# Dogfish3D_-_Z_Driver.net
KiCad netlist of a schematic drawn in Altium Designer
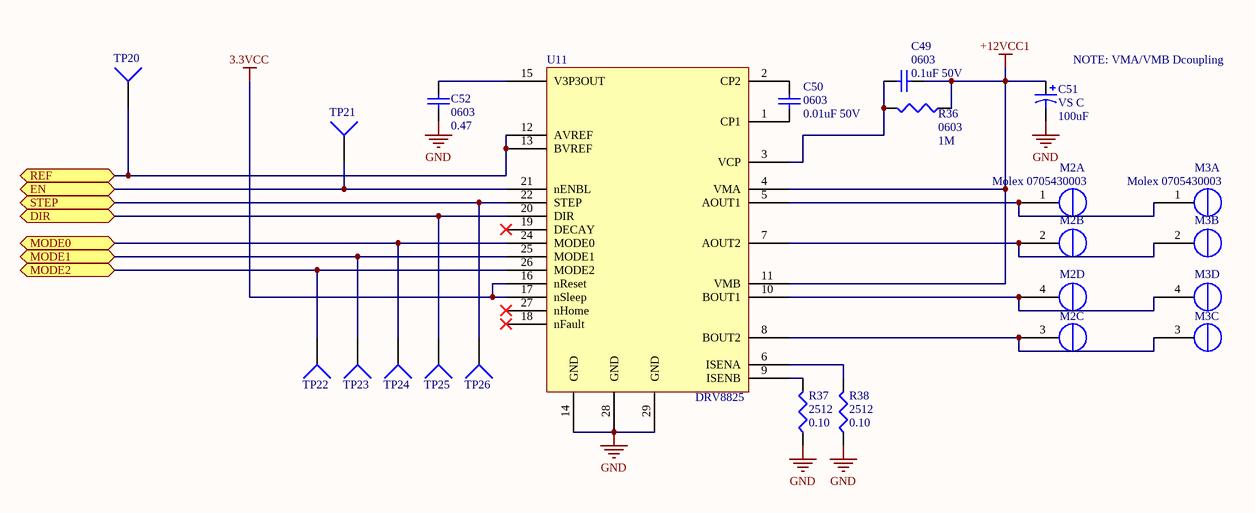
[diagram p0: Dogfish3D - Z Driver.SchDoc]

(export (version "E")
  (design (tool "Eeschema 10.0.6"))
  (components
    (comp (ref "C49")
      (value "0603")
      (footprint "1608[0603]")
      (description "Capacitor (Semiconductor SIM Model)")
      (fields (field (name "ALTIUM_VALUE") "0.1uF 50V") (field (name "PUBLISHER") "Altium Limited"))
      (libsource (lib "Miscellaneous Devices") (part "Cap Semi"))
    )
    (comp (ref "C50")
      (value "0603")
      (footprint "1608[0603]")
      (description "Capacitor (Semiconductor SIM Model)")
      (fields (field (name "ALTIUM_VALUE") "0.01uF 50V") (field (name "PUBLISHER") "Altium Limited"))
      (libsource (lib "Miscellaneous Devices") (part "Cap Semi"))
    )
    (comp (ref "C51")
      (value "VS C")
      (footprint "Panasonic VS C")
      (description "Polarized Capacitor (Radial)")
      (fields (field (name "ALTIUM_VALUE") "100uF") (field (name "PUBLISHER") "Altium Limited"))
      (libsource (lib "Miscellaneous Devices") (part "Cap Pol1"))
    )
    (comp (ref "C52")
      (value "0603")
      (footprint "1608[0603]")
      (description "Capacitor (Semiconductor SIM Model)")
      (fields (field (name "ALTIUM_VALUE") "0.47") (field (name "PUBLISHER") "Altium Limited"))
      (libsource (lib "Miscellaneous Devices") (part "Cap Semi"))
    )
    (comp (ref "M2")
      (value "Molex 0705430003")
      (footprint "Molex 0705430003")
      (description "Molex 4 Pin Clip Connector")
      (libsource (lib "ZMBo Schematic Library") (part "Molex 0705430003 Alt"))
    )
    (comp (ref "M3")
      (value "Molex 0705430003")
      (footprint "4POL254")
      (description "Molex 4 Pin Clip Connector")
      (libsource (lib "ZMBo Schematic Library") (part "Molex 0705430003 Alt"))
    )
    (comp (ref "R36")
      (value "0603")
      (footprint "J1-0603")
      (description "Resistor")
      (fields (field (name "ALTIUM_VALUE") "1M") (field (name "PUBLISHER") "Altium Limited"))
      (libsource (lib "Miscellaneous Devices") (part "Res3"))
    )
    (comp (ref "R37")
      (value "2512")
      (footprint "Resistor2512")
      (description "Resistor")
      (fields (field (name "ALTIUM_VALUE") "0.10") (field (name "PUBLISHER") "Altium Limited"))
      (libsource (lib "Miscellaneous Devices") (part "Res3"))
    )
    (comp (ref "R38")
      (value "2512")
      (footprint "Resistor2512")
      (description "Resistor")
      (fields (field (name "ALTIUM_VALUE") "0.10") (field (name "PUBLISHER") "Altium Limited"))
      (libsource (lib "Miscellaneous Devices") (part "Res3"))
    )
    (comp (ref "TP20")
      (value "TP4")
      (footprint "TP-2")
      (description "Socket")
      (fields (field (name "PUBLISHER") "Altium Limited"))
      (libsource (lib "ZMBo Schematic Library") (part "Socket"))
    )
    (comp (ref "TP21")
      (value "TP4")
      (footprint "TP-2")
      (description "Socket")
      (fields (field (name "PUBLISHER") "Altium Limited"))
      (libsource (lib "ZMBo Schematic Library") (part "Socket"))
    )
    (comp (ref "TP22")
      (value "TP4")
      (footprint "TP-2")
      (description "Socket")
      (fields (field (name "PUBLISHER") "Altium Limited"))
      (libsource (lib "ZMBo Schematic Library") (part "Socket"))
    )
    (comp (ref "TP23")
      (value "TP4")
      (footprint "TP-2")
      (description "Socket")
      (fields (field (name "PUBLISHER") "Altium Limited"))
      (libsource (lib "ZMBo Schematic Library") (part "Socket"))
    )
    (comp (ref "TP24")
      (value "TP4")
      (footprint "TP-2")
      (description "Socket")
      (fields (field (name "PUBLISHER") "Altium Limited"))
      (libsource (lib "ZMBo Schematic Library") (part "Socket"))
    )
    (comp (ref "TP25")
      (value "TP4")
      (footprint "TP-2")
      (description "Socket")
      (fields (field (name "PUBLISHER") "Altium Limited"))
      (libsource (lib "ZMBo Schematic Library") (part "Socket"))
    )
    (comp (ref "TP26")
      (value "TP4")
      (footprint "TP-2")
      (description "Socket")
      (fields (field (name "PUBLISHER") "Altium Limited"))
      (libsource (lib "ZMBo Schematic Library") (part "Socket"))
    )
    (comp (ref "U11")
      (value "DRV8825")
      (footprint "DRV8825")
      (description "DRV8825 Ti Stepper Driver")
      (libsource (lib "ZMBo Schematic Library") (part "DRV8825"))
    )
  )
  (nets
    (net (code "1") (name "+12VCC1") (class "Default")
      (node (ref "C49") (pin "1") (pinfunction "1_1") (pintype "passive"))
      (node (ref "C51") (pin "1") (pinfunction "1_1") (pintype "passive"))
      (node (ref "R36") (pin "1") (pinfunction "1_1") (pintype "passive"))
      (node (ref "U11") (pin "11") (pinfunction "VMB_11") (pintype "passive"))
      (node (ref "U11") (pin "4") (pinfunction "VMA_4") (pintype "passive"))
    )
    (net (code "2") (name "/DIR") (class "Default")
      (node (ref "TP25") (pin "1") (pinfunction "1_1") (pintype "passive"))
      (node (ref "U11") (pin "20") (pinfunction "DIR_20") (pintype "passive"))
    )
    (net (code "3") (name "/EN") (class "Default")
      (node (ref "TP21") (pin "1") (pinfunction "1_1") (pintype "passive"))
      (node (ref "U11") (pin "21") (pinfunction "nENBL_21") (pintype "passive"))
    )
    (net (code "4") (name "/MODE0") (class "Default")
      (node (ref "TP24") (pin "1") (pinfunction "1_1") (pintype "passive"))
      (node (ref "U11") (pin "24") (pinfunction "MODE0_24") (pintype "passive"))
    )
    (net (code "5") (name "/MODE1") (class "Default")
      (node (ref "TP23") (pin "1") (pinfunction "1_1") (pintype "passive"))
      (node (ref "U11") (pin "25") (pinfunction "MODE1_25") (pintype "passive"))
    )
    (net (code "6") (name "/MODE2") (class "Default")
      (node (ref "TP22") (pin "1") (pinfunction "1_1") (pintype "passive"))
      (node (ref "U11") (pin "26") (pinfunction "MODE2_26") (pintype "passive"))
    )
    (net (code "7") (name "/REF") (class "Default")
      (node (ref "TP20") (pin "1") (pinfunction "1_1") (pintype "passive"))
      (node (ref "U11") (pin "12") (pinfunction "AVREF_12") (pintype "passive"))
      (node (ref "U11") (pin "13") (pinfunction "BVREF_13") (pintype "passive"))
    )
    (net (code "8") (name "/STEP") (class "Default")
      (node (ref "TP26") (pin "1") (pinfunction "1_1") (pintype "passive"))
      (node (ref "U11") (pin "22") (pinfunction "STEP_22") (pintype "passive"))
    )
    (net (code "9") (name "3.3VCC") (class "Default")
      (node (ref "U11") (pin "16") (pinfunction "nReset_16") (pintype "passive"))
      (node (ref "U11") (pin "17") (pinfunction "nSleep_17") (pintype "passive"))
    )
    (net (code "10") (name "GND") (class "Default")
      (node (ref "C51") (pin "2") (pinfunction "2_2") (pintype "passive"))
      (node (ref "C52") (pin "1") (pinfunction "1_1") (pintype "passive"))
      (node (ref "R37") (pin "1") (pinfunction "1_1") (pintype "passive"))
      (node (ref "R38") (pin "1") (pinfunction "1_1") (pintype "passive"))
      (node (ref "U11") (pin "14") (pinfunction "GND_14") (pintype "passive"))
      (node (ref "U11") (pin "28") (pinfunction "GND_28") (pintype "passive"))
      (node (ref "U11") (pin "29") (pinfunction "GND_29") (pintype "passive"))
    )
    (net (code "11") (name "Net-(M2A-OUT2B)") (class "Default")
      (node (ref "M2") (pin "1") (pinfunction "OUT2B_1") (pintype "passive"))
      (node (ref "M3") (pin "1") (pinfunction "OUT2B_1") (pintype "passive"))
      (node (ref "U11") (pin "5") (pinfunction "AOUT1_5") (pintype "passive"))
    )
    (net (code "12") (name "Net-(M2B-OUT2A)") (class "Default")
      (node (ref "M2") (pin "2") (pinfunction "OUT2A_2") (pintype "passive"))
      (node (ref "M3") (pin "2") (pinfunction "OUT2A_2") (pintype "passive"))
      (node (ref "U11") (pin "7") (pinfunction "AOUT2_7") (pintype "passive"))
    )
    (net (code "13") (name "Net-(M2C-OUT1A)") (class "Default")
      (node (ref "M2") (pin "3") (pinfunction "OUT1A_3") (pintype "passive"))
      (node (ref "M3") (pin "3") (pinfunction "OUT1A_3") (pintype "passive"))
      (node (ref "U11") (pin "8") (pinfunction "BOUT2_8") (pintype "passive"))
    )
    (net (code "14") (name "Net-(M2D-OUT1B)") (class "Default")
      (node (ref "M2") (pin "4") (pinfunction "OUT1B_4") (pintype "passive"))
      (node (ref "M3") (pin "4") (pinfunction "OUT1B_4") (pintype "passive"))
      (node (ref "U11") (pin "10") (pinfunction "BOUT1_10") (pintype "passive"))
    )
    (net (code "15") (name "Net-(U11-CP1)") (class "Default")
      (node (ref "C50") (pin "1") (pinfunction "1_1") (pintype "passive"))
      (node (ref "U11") (pin "1") (pinfunction "CP1_1") (pintype "passive"))
    )
    (net (code "16") (name "Net-(U11-CP2)") (class "Default")
      (node (ref "C50") (pin "2") (pinfunction "2_2") (pintype "passive"))
      (node (ref "U11") (pin "2") (pinfunction "CP2_2") (pintype "passive"))
    )
    (net (code "17") (name "Net-(U11-ISENA)") (class "Default")
      (node (ref "R38") (pin "2") (pinfunction "2_2") (pintype "passive"))
      (node (ref "U11") (pin "6") (pinfunction "ISENA_6") (pintype "passive"))
    )
    (net (code "18") (name "Net-(U11-ISENB)") (class "Default")
      (node (ref "R37") (pin "2") (pinfunction "2_2") (pintype "passive"))
      (node (ref "U11") (pin "9") (pinfunction "ISENB_9") (pintype "passive"))
    )
    (net (code "19") (name "Net-(U11-V3P3OUT)") (class "Default")
      (node (ref "C52") (pin "2") (pinfunction "2_2") (pintype "passive"))
      (node (ref "U11") (pin "15") (pinfunction "V3P3OUT_15") (pintype "passive"))
    )
    (net (code "20") (name "Net-(U11-VCP)") (class "Default")
      (node (ref "C49") (pin "2") (pinfunction "2_2") (pintype "passive"))
      (node (ref "R36") (pin "2") (pinfunction "2_2") (pintype "passive"))
      (node (ref "U11") (pin "3") (pinfunction "VCP_3") (pintype "passive"))
    )
    (net (code "21") (name "unconnected-(U11-DECAY-Pad19)") (class "Default")
      (node (ref "U11") (pin "19") (pinfunction "DECAY_19") (pintype "passive+no_connect"))
    )
    (net (code "22") (name "unconnected-(U11-NC-Pad23)") (class "Default")
      (node (ref "U11") (pin "23") (pinfunction "NC_23") (pintype "passive"))
    )
    (net (code "23") (name "unconnected-(U11-nFault-Pad18)") (class "Default")
      (node (ref "U11") (pin "18") (pinfunction "nFault_18") (pintype "passive+no_connect"))
    )
    (net (code "24") (name "unconnected-(U11-nHome-Pad27)") (class "Default")
      (node (ref "U11") (pin "27") (pinfunction "nHome_27") (pintype "passive+no_connect"))
    )
  )
)
